# Sheet_ESP8266.net
KiCad netlist of a schematic drawn in Altium Designer
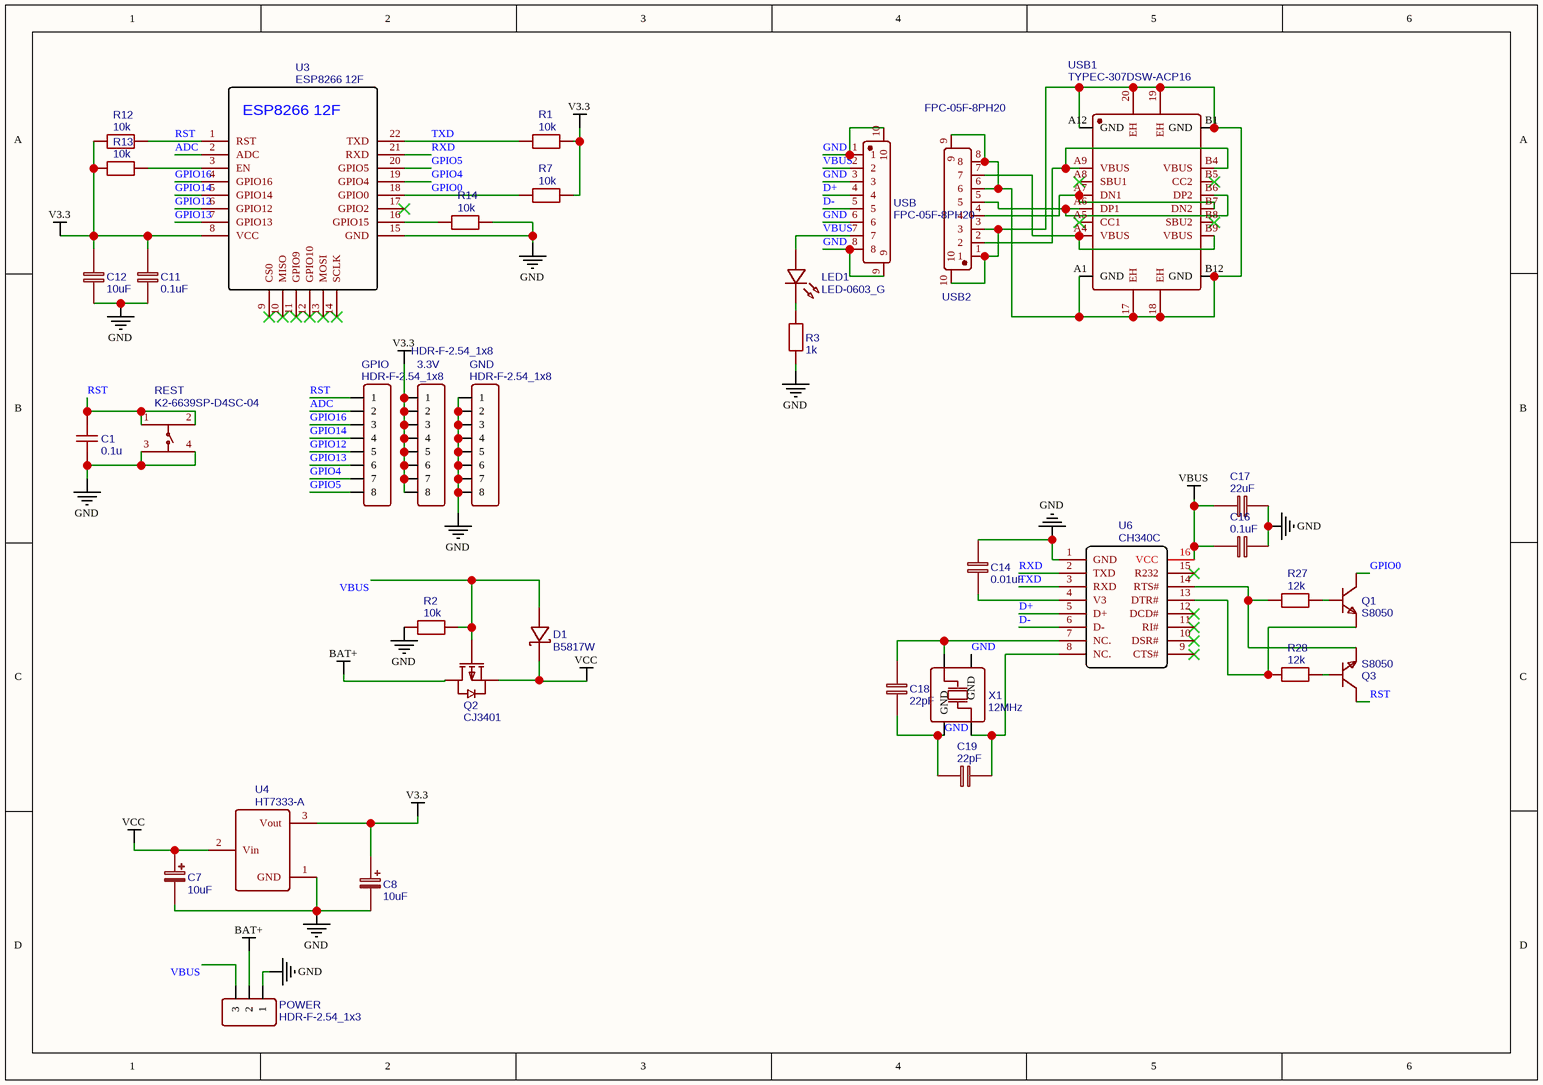
[diagram p0: Sheet_ESP8266开发板.schdoc]

(export (version "E")
  (design (tool "Eeschema 10.0.6"))
  (components
    (comp (ref "3.3V")
      (value "HDR-F-2.54_1x8")
      (fields (field (name "BOM_SUPPLIER PART") "C225505") (field (name "CONTRIBUTOR") "LCEDA_Lib"))
      (libsource (lib "altium-import") (part "root_0_HDR-F-2.54_1x8_"))
    )
    (comp (ref "C1")
      (value "0.1u")
      (fields (field (name "CONTRIBUTOR") "LCEDA_Lib"))
      (libsource (lib "altium-import") (part "root_1_0.1u_"))
    )
    (comp (ref "C7")
      (value "10uF")
      (fields (field (name "CONTRIBUTOR") "LCEDA_Lib"))
      (libsource (lib "altium-import") (part "root_3_10uF_"))
    )
    (comp (ref "C8")
      (value "10uF")
      (fields (field (name "CONTRIBUTOR") "LCEDA_Lib"))
      (libsource (lib "altium-import") (part "root_3_10uF_"))
    )
    (comp (ref "C11")
      (value "0.1uF")
      (fields (field (name "CONTRIBUTOR") "LCEDA_Lib"))
      (libsource (lib "altium-import") (part "root_1_0.1uF_"))
    )
    (comp (ref "C12")
      (value "10uF")
      (fields (field (name "CONTRIBUTOR") "LCEDA_Lib"))
      (libsource (lib "altium-import") (part "root_1_10uF_"))
    )
    (comp (ref "C14")
      (value "0.01uF")
      (fields (field (name "CONTRIBUTOR") "LCEDA_Lib"))
      (libsource (lib "altium-import") (part "root_1_0.01uF_"))
    )
    (comp (ref "C16")
      (value "0.1uF")
      (fields (field (name "CONTRIBUTOR") "LCEDA_Lib"))
      (libsource (lib "altium-import") (part "root_2_0.1uF_"))
    )
    (comp (ref "C17")
      (value "22uF")
      (fields (field (name "CONTRIBUTOR") "LCEDA_Lib"))
      (libsource (lib "altium-import") (part "root_2_22uF_"))
    )
    (comp (ref "C18")
      (value "22pF")
      (fields (field (name "CONTRIBUTOR") "LCEDA_Lib"))
      (libsource (lib "altium-import") (part "root_1_22pF_"))
    )
    (comp (ref "C19")
      (value "22pF")
      (fields (field (name "CONTRIBUTOR") "LCEDA_Lib"))
      (libsource (lib "altium-import") (part "root_2_22pF_"))
    )
    (comp (ref "D1")
      (value "B5817W")
      (fields (field (name "BOM_SUPPLIER PART") "C179719") (field (name "CONTRIBUTOR") "LCSC"))
      (libsource (lib "altium-import") (part "root_1_B5817W_"))
    )
    (comp (ref "GND")
      (value "HDR-F-2.54_1x8")
      (fields (field (name "BOM_SUPPLIER PART") "C225505") (field (name "CONTRIBUTOR") "LCEDA_Lib"))
      (libsource (lib "altium-import") (part "root_0_HDR-F-2.54_1x8_"))
    )
    (comp (ref "GPIO")
      (value "HDR-F-2.54_1x8")
      (fields (field (name "BOM_SUPPLIER PART") "C225505") (field (name "CONTRIBUTOR") "LCEDA_Lib"))
      (libsource (lib "altium-import") (part "root_0_HDR-F-2.54_1x8_"))
    )
    (comp (ref "LED1")
      (value "LED-0603_G")
      (fields
        (field (name "BOM_MANUFACTURER PART") "19-217/GHC-YR1S2/3T")
        (field (name "BOM_SUPPLIER PART") "C72043")
        (field (name "CONTRIBUTOR") "LCEDA_Lib")
      )
      (libsource (lib "altium-import") (part "root_3_LED-0603_G_"))
    )
    (comp (ref "POWER")
      (value "HDR-F-2.54_1x3")
      (fields (field (name "BOM_SUPPLIER PART") "C146690") (field (name "CONTRIBUTOR") "LCEDA_Lib"))
      (libsource (lib "altium-import") (part "root_3_HDR-F-2.54_1x3_"))
    )
    (comp (ref "Q1")
      (value "S8050")
      (fields (field (name "BOM_SUPPLIER PART") "C916390") (field (name "CONTRIBUTOR") "LCSC"))
      (libsource (lib "") (part "root_0_S8050__1"))
    )
    (comp (ref "Q2")
      (value "CJ3401")
      (fields (field (name "BOM_SUPPLIER PART") "C13799") (field (name "CONTRIBUTOR") "lwjyl"))
      (libsource (lib "altium-import") (part "root_3_CJ3401_"))
    )
    (comp (ref "Q3")
      (value "S8050")
      (fields (field (name "BOM_SUPPLIER PART") "C916390") (field (name "CONTRIBUTOR") "LCSC"))
      (libsource (lib "altium-import") (part "root_0_S8050_"))
    )
    (comp (ref "R1")
      (value "10k")
      (fields (field (name "CONTRIBUTOR") "LCEDA_Lib"))
      (libsource (lib "altium-import") (part "root_2_10k_"))
    )
    (comp (ref "R2")
      (value "10k")
      (fields (field (name "CONTRIBUTOR") "LCEDA_Lib"))
      (libsource (lib "altium-import") (part "root_0_10k_"))
    )
    (comp (ref "R3")
      (value "1k")
      (fields (field (name "CONTRIBUTOR") "LCEDA_Lib"))
      (libsource (lib "altium-import") (part "root_1_1k_"))
    )
    (comp (ref "R7")
      (value "10k")
      (fields (field (name "CONTRIBUTOR") "LCEDA_Lib"))
      (libsource (lib "altium-import") (part "root_2_10k_"))
    )
    (comp (ref "R12")
      (value "10k")
      (fields (field (name "CONTRIBUTOR") "LCEDA_Lib"))
      (libsource (lib "altium-import") (part "root_2_10k_"))
    )
    (comp (ref "R13")
      (value "10k")
      (fields (field (name "CONTRIBUTOR") "LCEDA_Lib"))
      (libsource (lib "altium-import") (part "root_2_10k_"))
    )
    (comp (ref "R14")
      (value "10k")
      (fields (field (name "CONTRIBUTOR") "LCEDA_Lib"))
      (libsource (lib "altium-import") (part "root_2_10k_"))
    )
    (comp (ref "R27")
      (value "12k")
      (fields (field (name "CONTRIBUTOR") "LCEDA_Lib"))
      (libsource (lib "altium-import") (part "root_0_12k_"))
    )
    (comp (ref "R28")
      (value "12k")
      (fields (field (name "CONTRIBUTOR") "LCEDA_Lib"))
      (libsource (lib "altium-import") (part "root_0_12k_"))
    )
    (comp (ref "REST")
      (value "K2-6639SP-D4SC-04")
      (fields (field (name "BOM_SUPPLIER PART") "C191626") (field (name "CONTRIBUTOR") "LCSC"))
      (libsource (lib "altium-import") (part "root_0_K2-6639SP-D4SC-04_"))
    )
    (comp (ref "U3")
      (value "ESP8266 12F")
      (fields (field (name "CONTRIBUTOR") "gerdmuller.de"))
      (libsource (lib "altium-import") (part "root_0_ESP8266 12F_"))
    )
    (comp (ref "U4")
      (value "HT7333-A")
      (fields (field (name "BOM_SUPPLIER PART") "C21583"))
      (libsource (lib "altium-import") (part "root_0_HT7333-A_"))
    )
    (comp (ref "U6")
      (value "CH340C")
      (fields (field (name "BOM_SUPPLIER PART") "C84681"))
      (libsource (lib "altium-import") (part "root_0_CH340C_"))
    )
    (comp (ref "USB")
      (value "FPC-05F-8PH20")
      (fields (field (name "BOM_SUPPLIER PART") "C2856797") (field (name "CONTRIBUTOR") "LCSC"))
      (libsource (lib "altium-import") (part "root_0_FPC-05F-8PH20_"))
    )
    (comp (ref "USB1")
      (value "TYPEC-307DSW-ACP16")
      (fields (field (name "BOM_SUPPLIER PART") "C2840402") (field (name "CONTRIBUTOR") "LCSC"))
      (libsource (lib "altium-import") (part "root_0_TYPEC-307DSW-ACP16_"))
    )
    (comp (ref "USB2")
      (value "FPC-05F-8PH20")
      (fields (field (name "BOM_SUPPLIER PART") "C2856797") (field (name "CONTRIBUTOR") "LCSC"))
      (libsource (lib "altium-import") (part "root_2_FPC-05F-8PH20_"))
    )
    (comp (ref "X1")
      (value "12MHz")
      (fields
        (field (name "BOM_MANUFACTURER PART") "7M1209LCSC-DDJ4S")
        (field (name "BOM_SUPPLIER PART") "C90900")
        (field (name "CONTRIBUTOR") "LCSC")
      )
      (libsource (lib "altium-import") (part "root_3_12MHz_"))
    )
  )
  (nets
    (net (code "1") (name "/ADC") (class "Default")
      (node (ref "GPIO") (pin "2") (pinfunction "2_2") (pintype "passive"))
      (node (ref "U3") (pin "2") (pinfunction "ADC_2") (pintype "passive"))
    )
    (net (code "2") (name "/D+") (class "Default")
      (node (ref "U6") (pin "5") (pinfunction "D+_5") (pintype "passive"))
      (node (ref "USB") (pin "4") (pinfunction "4_4") (pintype "passive"))
    )
    (net (code "3") (name "/D-") (class "Default")
      (node (ref "U6") (pin "6") (pinfunction "D-_6") (pintype "passive"))
      (node (ref "USB") (pin "5") (pinfunction "5_5") (pintype "passive"))
    )
    (net (code "4") (name "/GPIO0") (class "Default")
      (node (ref "Q1") (pin "3") (pinfunction "C_3") (pintype "passive"))
      (node (ref "R7") (pin "2") (pinfunction "2_2") (pintype "passive"))
      (node (ref "U3") (pin "18") (pinfunction "GPIO0_18") (pintype "passive"))
    )
    (net (code "5") (name "/GPIO4") (class "Default")
      (node (ref "GPIO") (pin "7") (pinfunction "7_7") (pintype "passive"))
      (node (ref "U3") (pin "19") (pinfunction "GPIO4_19") (pintype "passive"))
    )
    (net (code "6") (name "/GPIO5") (class "Default")
      (node (ref "GPIO") (pin "8") (pinfunction "8_8") (pintype "passive"))
      (node (ref "U3") (pin "20") (pinfunction "GPIO5_20") (pintype "passive"))
    )
    (net (code "7") (name "/GPIO12") (class "Default")
      (node (ref "GPIO") (pin "5") (pinfunction "5_5") (pintype "passive"))
      (node (ref "U3") (pin "6") (pinfunction "GPIO12_6") (pintype "passive"))
    )
    (net (code "8") (name "/GPIO13") (class "Default")
      (node (ref "GPIO") (pin "6") (pinfunction "6_6") (pintype "passive"))
      (node (ref "U3") (pin "7") (pinfunction "GPIO13_7") (pintype "passive"))
    )
    (net (code "9") (name "/GPIO14") (class "Default")
      (node (ref "GPIO") (pin "4") (pinfunction "4_4") (pintype "passive"))
      (node (ref "U3") (pin "5") (pinfunction "GPIO14_5") (pintype "passive"))
    )
    (net (code "10") (name "/GPIO16") (class "Default")
      (node (ref "GPIO") (pin "3") (pinfunction "3_3") (pintype "passive"))
      (node (ref "U3") (pin "4") (pinfunction "GPIO16_4") (pintype "passive"))
    )
    (net (code "11") (name "/RST") (class "Default")
      (node (ref "C1") (pin "2") (pinfunction "2_2") (pintype "passive"))
      (node (ref "GPIO") (pin "1") (pinfunction "1_1") (pintype "passive"))
      (node (ref "Q3") (pin "3") (pinfunction "C_3") (pintype "passive"))
      (node (ref "R12") (pin "1") (pinfunction "1_1") (pintype "passive"))
      (node (ref "REST") (pin "1") (pinfunction "1_1") (pintype "passive"))
      (node (ref "REST") (pin "2") (pinfunction "2_2") (pintype "passive"))
      (node (ref "U3") (pin "1") (pinfunction "RST_1") (pintype "passive"))
    )
    (net (code "12") (name "/RXD") (class "Default")
      (node (ref "U3") (pin "21") (pinfunction "RXD_21") (pintype "passive"))
      (node (ref "U6") (pin "2") (pinfunction "TXD_2") (pintype "passive"))
    )
    (net (code "13") (name "/TXD") (class "Default")
      (node (ref "R1") (pin "2") (pinfunction "2_2") (pintype "passive"))
      (node (ref "U3") (pin "22") (pinfunction "TXD_22") (pintype "passive"))
      (node (ref "U6") (pin "3") (pinfunction "RXD_3") (pintype "passive"))
    )
    (net (code "14") (name "BAT+") (class "Default")
      (node (ref "POWER") (pin "2") (pinfunction "2_2") (pintype "passive"))
      (node (ref "Q2") (pin "3") (pinfunction "D_3") (pintype "passive"))
    )
    (net (code "15") (name "GND") (class "Default")
      (node (ref "C1") (pin "1") (pinfunction "1_1") (pintype "passive"))
      (node (ref "C11") (pin "1") (pinfunction "1_1") (pintype "passive"))
      (node (ref "C12") (pin "1") (pinfunction "1_1") (pintype "passive"))
      (node (ref "C14") (pin "2") (pinfunction "2_2") (pintype "passive"))
      (node (ref "C16") (pin "1") (pinfunction "1_1") (pintype "passive"))
      (node (ref "C17") (pin "1") (pinfunction "1_1") (pintype "passive"))
      (node (ref "C18") (pin "1") (pinfunction "1_1") (pintype "passive"))
      (node (ref "C19") (pin "2") (pinfunction "2_2") (pintype "passive"))
      (node (ref "C7") (pin "2") (pinfunction "2_2") (pintype "passive"))
      (node (ref "C8") (pin "2") (pinfunction "2_2") (pintype "passive"))
      (node (ref "GND") (pin "1") (pinfunction "1_1") (pintype "passive"))
      (node (ref "GND") (pin "2") (pinfunction "2_2") (pintype "passive"))
      (node (ref "GND") (pin "3") (pinfunction "3_3") (pintype "passive"))
      (node (ref "GND") (pin "4") (pinfunction "4_4") (pintype "passive"))
      (node (ref "GND") (pin "5") (pinfunction "5_5") (pintype "passive"))
      (node (ref "GND") (pin "6") (pinfunction "6_6") (pintype "passive"))
      (node (ref "GND") (pin "7") (pinfunction "7_7") (pintype "passive"))
      (node (ref "GND") (pin "8") (pinfunction "8_8") (pintype "passive"))
      (node (ref "POWER") (pin "1") (pinfunction "1_1") (pintype "passive"))
      (node (ref "R14") (pin "1") (pinfunction "1_1") (pintype "passive"))
      (node (ref "R2") (pin "1") (pinfunction "1_1") (pintype "passive"))
      (node (ref "R3") (pin "1") (pinfunction "1_1") (pintype "passive"))
      (node (ref "REST") (pin "3") (pinfunction "3_3") (pintype "passive"))
      (node (ref "REST") (pin "4") (pinfunction "4_4") (pintype "passive"))
      (node (ref "U3") (pin "15") (pinfunction "GND_15") (pintype "passive"))
      (node (ref "U4") (pin "1") (pinfunction "GND_1") (pintype "passive"))
      (node (ref "U6") (pin "1") (pinfunction "GND_1") (pintype "passive"))
      (node (ref "USB") (pin "1") (pinfunction "1_1") (pintype "passive"))
      (node (ref "USB") (pin "10") (pinfunction "10_10") (pintype "passive"))
      (node (ref "USB") (pin "3") (pinfunction "3_3") (pintype "passive"))
      (node (ref "USB") (pin "6") (pinfunction "6_6") (pintype "passive"))
      (node (ref "USB") (pin "8") (pinfunction "8_8") (pintype "passive"))
      (node (ref "USB") (pin "9") (pinfunction "9_9") (pintype "passive"))
      (node (ref "X1") (pin "2") (pinfunction "GND_2") (pintype "passive"))
      (node (ref "X1") (pin "4") (pinfunction "GND_4") (pintype "passive"))
    )
    (net (code "16") (name "Net-(LED1-Pad2)") (class "Default")
      (node (ref "LED1") (pin "2") (pinfunction "2_2") (pintype "passive"))
      (node (ref "R3") (pin "2") (pinfunction "2_2") (pintype "passive"))
    )
    (net (code "17") (name "Net-(Q1-B)") (class "Default")
      (node (ref "Q1") (pin "1") (pinfunction "B_1") (pintype "passive"))
      (node (ref "R27") (pin "2") (pinfunction "2_2") (pintype "passive"))
    )
    (net (code "18") (name "Net-(Q1-E)") (class "Default")
      (node (ref "Q1") (pin "2") (pinfunction "E_2") (pintype "passive"))
      (node (ref "R28") (pin "1") (pinfunction "1_1") (pintype "passive"))
      (node (ref "U6") (pin "13") (pinfunction "DTR#_13") (pintype "passive"))
    )
    (net (code "19") (name "Net-(Q3-B)") (class "Default")
      (node (ref "Q3") (pin "1") (pinfunction "B_1") (pintype "passive"))
      (node (ref "R28") (pin "2") (pinfunction "2_2") (pintype "passive"))
    )
    (net (code "20") (name "Net-(Q3-E)") (class "Default")
      (node (ref "Q3") (pin "2") (pinfunction "E_2") (pintype "passive"))
      (node (ref "R27") (pin "1") (pinfunction "1_1") (pintype "passive"))
      (node (ref "U6") (pin "14") (pinfunction "RTS#_14") (pintype "passive"))
    )
    (net (code "21") (name "Net-(U3-EN)") (class "Default")
      (node (ref "R13") (pin "1") (pinfunction "1_1") (pintype "passive"))
      (node (ref "U3") (pin "3") (pinfunction "EN_3") (pintype "passive"))
    )
    (net (code "22") (name "Net-(U3-GPIO15)") (class "Default")
      (node (ref "R14") (pin "2") (pinfunction "2_2") (pintype "passive"))
      (node (ref "U3") (pin "16") (pinfunction "GPIO15_16") (pintype "passive"))
    )
    (net (code "23") (name "Net-(U6-V3)") (class "Default")
      (node (ref "C14") (pin "1") (pinfunction "1_1") (pintype "passive"))
      (node (ref "U6") (pin "4") (pinfunction "V3_4") (pintype "passive"))
    )
    (net (code "24") (name "Net-(USB1-DN1)") (class "Default")
      (node (ref "USB1") (pin "A7") (pinfunction "DN1_A7") (pintype "passive"))
      (node (ref "USB1") (pin "B7") (pinfunction "DN2_B7") (pintype "passive"))
      (node (ref "USB2") (pin "4") (pinfunction "4_4") (pintype "passive"))
    )
    (net (code "25") (name "Net-(USB1-DP1)") (class "Default")
      (node (ref "USB1") (pin "A6") (pinfunction "DP1_A6") (pintype "passive"))
      (node (ref "USB1") (pin "B6") (pinfunction "DP2_B6") (pintype "passive"))
      (node (ref "USB2") (pin "5") (pinfunction "5_5") (pintype "passive"))
    )
    (net (code "26") (name "Net-(USB1-EH-Pad17)") (class "Default")
      (node (ref "USB1") (pin "17") (pinfunction "EH_17") (pintype "passive"))
      (node (ref "USB1") (pin "18") (pinfunction "EH_18") (pintype "passive"))
      (node (ref "USB1") (pin "19") (pinfunction "EH_19") (pintype "passive"))
      (node (ref "USB1") (pin "20") (pinfunction "EH_20") (pintype "passive"))
      (node (ref "USB1") (pin "A1") (pinfunction "GND_A1") (pintype "passive"))
      (node (ref "USB1") (pin "A12") (pinfunction "GND_A12") (pintype "passive"))
      (node (ref "USB1") (pin "B1") (pinfunction "GND_B1") (pintype "passive"))
      (node (ref "USB1") (pin "B12") (pinfunction "GND_B12") (pintype "passive"))
      (node (ref "USB2") (pin "1") (pinfunction "1_1") (pintype "passive"))
      (node (ref "USB2") (pin "10") (pinfunction "10_10") (pintype "passive"))
      (node (ref "USB2") (pin "3") (pinfunction "3_3") (pintype "passive"))
      (node (ref "USB2") (pin "6") (pinfunction "6_6") (pintype "passive"))
      (node (ref "USB2") (pin "8") (pinfunction "8_8") (pintype "passive"))
      (node (ref "USB2") (pin "9") (pinfunction "9_9") (pintype "passive"))
    )
    (net (code "27") (name "Net-(USB1-VBUS-PadA4)") (class "Default")
      (node (ref "USB1") (pin "A4") (pinfunction "VBUS_A4") (pintype "passive"))
      (node (ref "USB1") (pin "B9") (pinfunction "VBUS_B9") (pintype "passive"))
      (node (ref "USB2") (pin "7") (pinfunction "7_7") (pintype "passive"))
    )
    (net (code "28") (name "Net-(USB1-VBUS-PadA9)") (class "Default")
      (node (ref "USB1") (pin "A9") (pinfunction "VBUS_A9") (pintype "passive"))
      (node (ref "USB1") (pin "B4") (pinfunction "VBUS_B4") (pintype "passive"))
      (node (ref "USB2") (pin "2") (pinfunction "2_2") (pintype "passive"))
    )
    (net (code "29") (name "Net-(X1-OSC1)") (class "Default")
      (node (ref "C18") (pin "2") (pinfunction "2_2") (pintype "passive"))
      (node (ref "U6") (pin "7") (pinfunction "NC._7") (pintype "passive"))
      (node (ref "X1") (pin "1") (pinfunction "OSC1_1") (pintype "passive"))
    )
    (net (code "30") (name "Net-(X1-OSC2)") (class "Default")
      (node (ref "C19") (pin "1") (pinfunction "1_1") (pintype "passive"))
      (node (ref "U6") (pin "8") (pinfunction "NC._8") (pintype "passive"))
      (node (ref "X1") (pin "3") (pinfunction "OSC2_3") (pintype "passive"))
    )
    (net (code "31") (name "V3.3") (class "Default")
      (node (ref "3.3V") (pin "1") (pinfunction "1_1") (pintype "passive"))
      (node (ref "3.3V") (pin "2") (pinfunction "2_2") (pintype "passive"))
      (node (ref "3.3V") (pin "3") (pinfunction "3_3") (pintype "passive"))
      (node (ref "3.3V") (pin "4") (pinfunction "4_4") (pintype "passive"))
      (node (ref "3.3V") (pin "5") (pinfunction "5_5") (pintype "passive"))
      (node (ref "3.3V") (pin "6") (pinfunction "6_6") (pintype "passive"))
      (node (ref "3.3V") (pin "7") (pinfunction "7_7") (pintype "passive"))
      (node (ref "3.3V") (pin "8") (pinfunction "8_8") (pintype "passive"))
      (node (ref "C11") (pin "2") (pinfunction "2_2") (pintype "passive"))
      (node (ref "C12") (pin "2") (pinfunction "2_2") (pintype "passive"))
      (node (ref "C8") (pin "1") (pinfunction "1_1") (pintype "passive"))
      (node (ref "R1") (pin "1") (pinfunction "1_1") (pintype "passive"))
      (node (ref "R12") (pin "2") (pinfunction "2_2") (pintype "passive"))
      (node (ref "R13") (pin "2") (pinfunction "2_2") (pintype "passive"))
      (node (ref "R7") (pin "1") (pinfunction "1_1") (pintype "passive"))
      (node (ref "U3") (pin "8") (pinfunction "VCC_8") (pintype "passive"))
      (node (ref "U4") (pin "3") (pinfunction "Vout_3") (pintype "passive"))
    )
    (net (code "32") (name "VBUS") (class "Default")
      (node (ref "C16") (pin "2") (pinfunction "2_2") (pintype "passive"))
      (node (ref "C17") (pin "2") (pinfunction "2_2") (pintype "passive"))
      (node (ref "D1") (pin "2") (pinfunction "A_2") (pintype "passive"))
      (node (ref "LED1") (pin "1") (pinfunction "1_1") (pintype "passive"))
      (node (ref "POWER") (pin "3") (pinfunction "3_3") (pintype "passive"))
      (node (ref "Q2") (pin "1") (pinfunction "G_1") (pintype "passive"))
      (node (ref "R2") (pin "2") (pinfunction "2_2") (pintype "passive"))
      (node (ref "U6") (pin "16") (pinfunction "VCC_16") (pintype "passive"))
      (node (ref "USB") (pin "2") (pinfunction "2_2") (pintype "passive"))
      (node (ref "USB") (pin "7") (pinfunction "7_7") (pintype "passive"))
    )
    (net (code "33") (name "VCC") (class "Default")
      (node (ref "C7") (pin "1") (pinfunction "1_1") (pintype "passive"))
      (node (ref "D1") (pin "1") (pinfunction "K_1") (pintype "passive"))
      (node (ref "Q2") (pin "2") (pinfunction "S_2") (pintype "passive"))
      (node (ref "U4") (pin "2") (pinfunction "Vin_2") (pintype "passive"))
    )
    (net (code "34") (name "unconnected-(U3-CS0-Pad9)") (class "Default")
      (node (ref "U3") (pin "9") (pinfunction "CS0_9") (pintype "passive+no_connect"))
    )
    (net (code "35") (name "unconnected-(U3-GPIO2-Pad17)") (class "Default")
      (node (ref "U3") (pin "17") (pinfunction "GPIO2_17") (pintype "passive+no_connect"))
    )
    (net (code "36") (name "unconnected-(U3-GPIO9-Pad11)") (class "Default")
      (node (ref "U3") (pin "11") (pinfunction "GPIO9_11") (pintype "passive+no_connect"))
    )
    (net (code "37") (name "unconnected-(U3-GPIO10-Pad12)") (class "Default")
      (node (ref "U3") (pin "12") (pinfunction "GPIO10_12") (pintype "passive+no_connect"))
    )
    (net (code "38") (name "unconnected-(U3-MISO-Pad10)") (class "Default")
      (node (ref "U3") (pin "10") (pinfunction "MISO_10") (pintype "passive+no_connect"))
    )
    (net (code "39") (name "unconnected-(U3-MOSI-Pad13)") (class "Default")
      (node (ref "U3") (pin "13") (pinfunction "MOSI_13") (pintype "passive+no_connect"))
    )
    (net (code "40") (name "unconnected-(U3-SCLK-Pad14)") (class "Default")
      (node (ref "U3") (pin "14") (pinfunction "SCLK_14") (pintype "passive+no_connect"))
    )
    (net (code "41") (name "unconnected-(U6-CTS#-Pad9)") (class "Default")
      (node (ref "U6") (pin "9") (pinfunction "CTS#_9") (pintype "passive+no_connect"))
    )
    (net (code "42") (name "unconnected-(U6-DCD#-Pad12)") (class "Default")
      (node (ref "U6") (pin "12") (pinfunction "DCD#_12") (pintype "passive+no_connect"))
    )
    (net (code "43") (name "unconnected-(U6-DSR#-Pad10)") (class "Default")
      (node (ref "U6") (pin "10") (pinfunction "DSR#_10") (pintype "passive+no_connect"))
    )
    (net (code "44") (name "unconnected-(U6-R232-Pad15)") (class "Default")
      (node (ref "U6") (pin "15") (pinfunction "R232_15") (pintype "passive+no_connect"))
    )
    (net (code "45") (name "unconnected-(U6-RI#-Pad11)") (class "Default")
      (node (ref "U6") (pin "11") (pinfunction "RI#_11") (pintype "passive+no_connect"))
    )
    (net (code "46") (name "unconnected-(USB1-CC1-PadA5)") (class "Default")
      (node (ref "USB1") (pin "A5") (pinfunction "CC1_A5") (pintype "passive+no_connect"))
    )
    (net (code "47") (name "unconnected-(USB1-CC2-PadB5)") (class "Default")
      (node (ref "USB1") (pin "B5") (pinfunction "CC2_B5") (pintype "passive+no_connect"))
    )
    (net (code "48") (name "unconnected-(USB1-SBU1-PadA8)") (class "Default")
      (node (ref "USB1") (pin "A8") (pinfunction "SBU1_A8") (pintype "passive+no_connect"))
    )
    (net (code "49") (name "unconnected-(USB1-SBU2-PadB8)") (class "Default")
      (node (ref "USB1") (pin "B8") (pinfunction "SBU2_B8") (pintype "passive+no_connect"))
    )
  )
)
